# KEYb_final-rev01.net
KiCad netlist of a schematic drawn in EAGLE
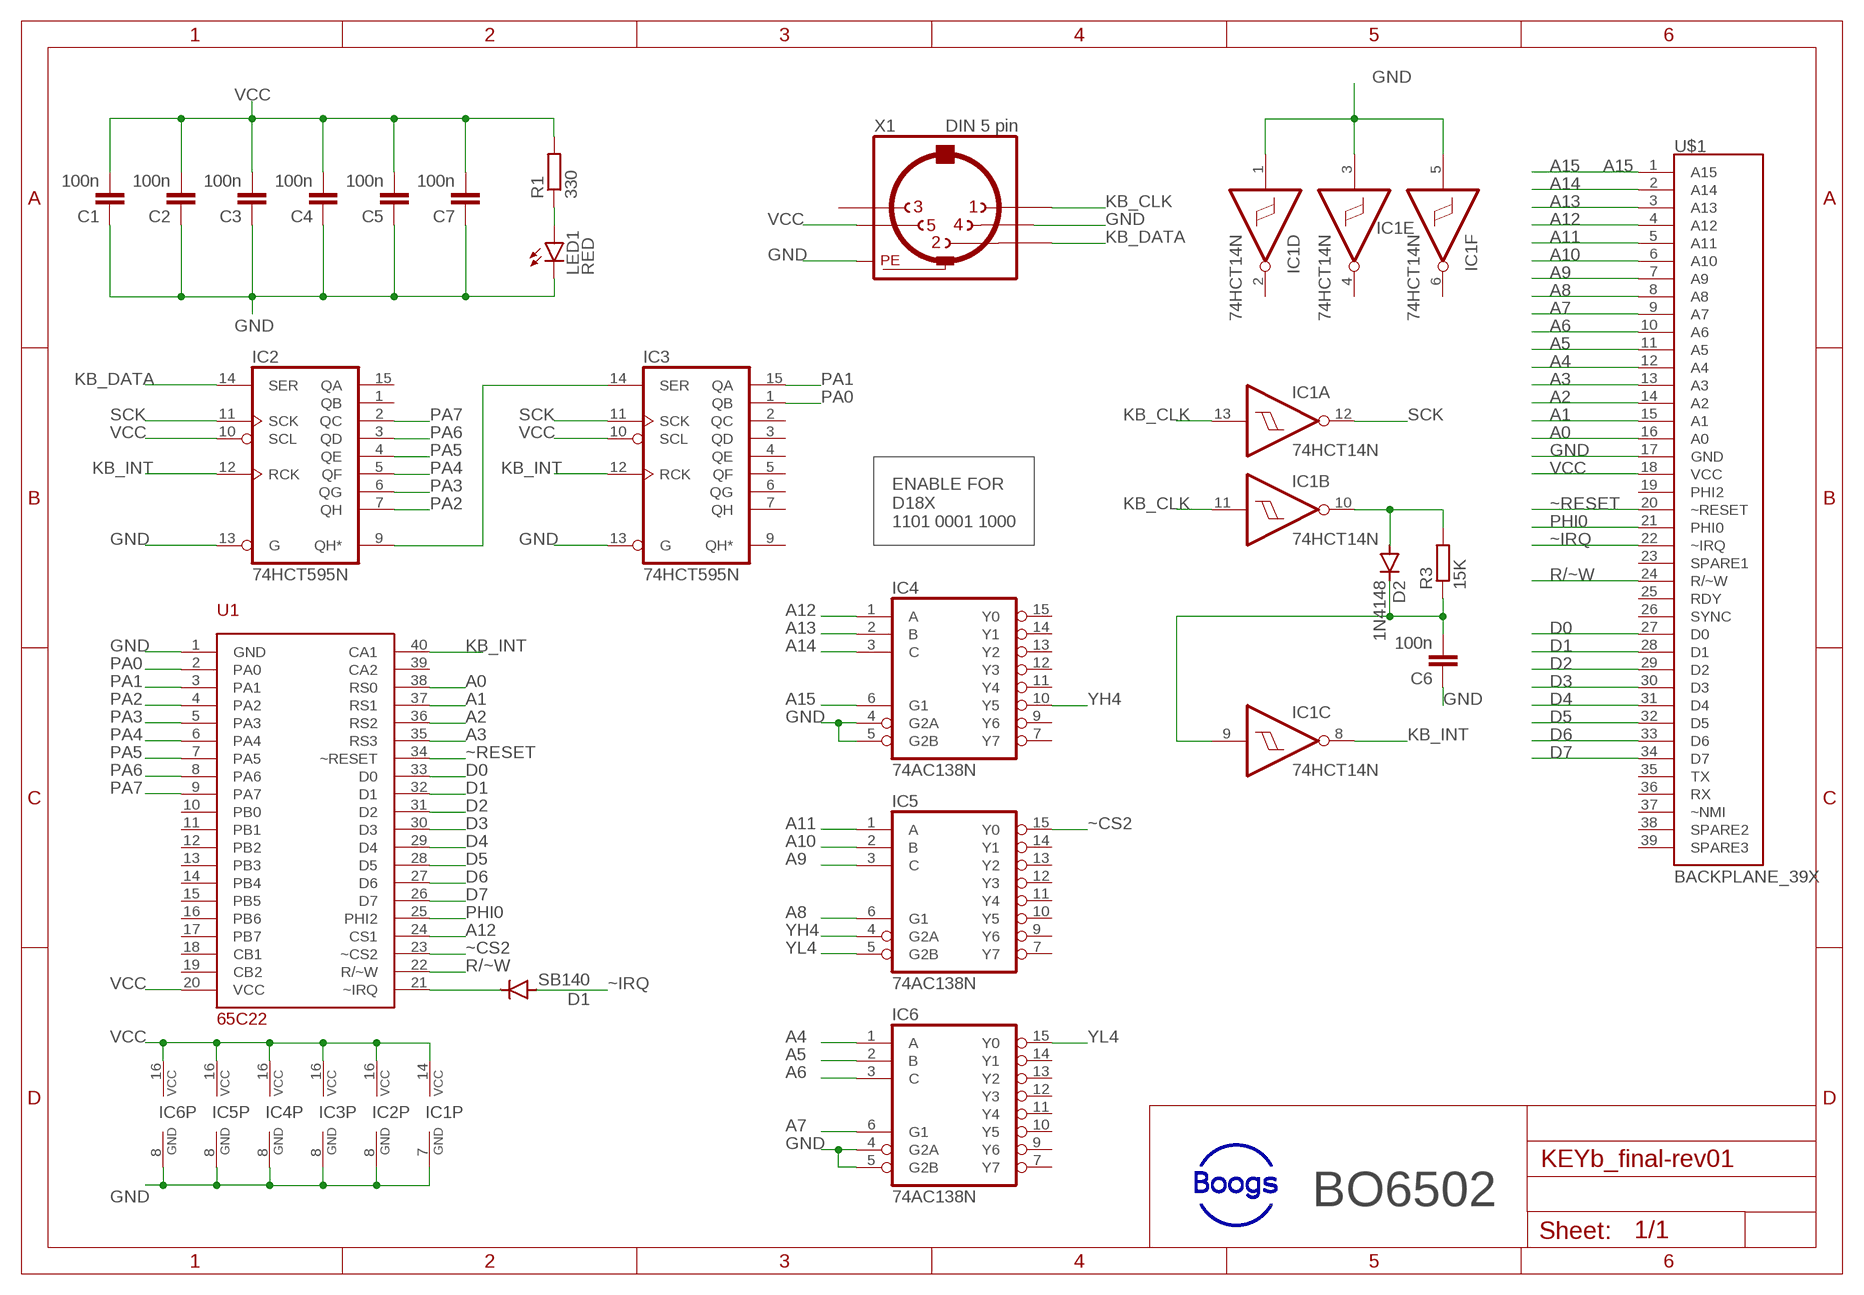
[diagram p0: schematic, sheet 1]

(export (version "E")
  (design (tool "Eeschema 10.0.6"))
  (components
    (comp (ref "C1")
      (value "100n")
      (footprint "eagle-import:C025-025X050")
      (libsource (lib "eagle-import") (part "C-EU025-025X050"))
    )
    (comp (ref "C2")
      (value "100n")
      (footprint "eagle-import:C025-025X050")
      (libsource (lib "eagle-import") (part "C-EU025-025X050"))
    )
    (comp (ref "C3")
      (value "100n")
      (footprint "eagle-import:C025-025X050")
      (libsource (lib "eagle-import") (part "C-EU025-025X050"))
    )
    (comp (ref "C4")
      (value "100n")
      (footprint "eagle-import:C025-025X050")
      (libsource (lib "eagle-import") (part "C-EU025-025X050"))
    )
    (comp (ref "C5")
      (value "100n")
      (footprint "eagle-import:C025-025X050")
      (libsource (lib "eagle-import") (part "C-EU025-025X050"))
    )
    (comp (ref "C6")
      (value "100n")
      (footprint "eagle-import:C025-025X050")
      (libsource (lib "eagle-import") (part "C-EU025-025X050"))
    )
    (comp (ref "C7")
      (value "100n")
      (footprint "eagle-import:C025-025X050")
      (libsource (lib "eagle-import") (part "C-EU025-025X050"))
    )
    (comp (ref "D1")
      (value "SB140")
      (footprint "eagle-import:DO41-10")
      (libsource (lib "eagle-import") (part "1N4004"))
    )
    (comp (ref "D2")
      (value "1N4148")
      (footprint "eagle-import:DO35-7")
      (libsource (lib "eagle-import") (part "1N4148DO35-7"))
    )
    (comp (ref "IC1")
      (value "74HCT14N")
      (footprint "eagle-import:DIL14")
      (libsource (lib "eagle-import") (part "7414NHCT"))
    )
    (comp (ref "IC2")
      (value "74HCT595N")
      (footprint "eagle-import:DIL16")
      (libsource (lib "eagle-import") (part "74595NHCT"))
    )
    (comp (ref "IC3")
      (value "74HCT595N")
      (footprint "eagle-import:DIL16")
      (libsource (lib "eagle-import") (part "74595NHCT"))
    )
    (comp (ref "IC4")
      (value "74AC138N")
      (footprint "eagle-import:DIL16")
      (libsource (lib "eagle-import") (part "74138NAC"))
    )
    (comp (ref "IC5")
      (value "74AC138N")
      (footprint "eagle-import:DIL16")
      (libsource (lib "eagle-import") (part "74138NAC"))
    )
    (comp (ref "IC6")
      (value "74AC138N")
      (footprint "eagle-import:DIL16")
      (libsource (lib "eagle-import") (part "74138NAC"))
    )
    (comp (ref "LED1")
      (value "RED")
      (footprint "eagle-import:LED5MM")
      (libsource (lib "eagle-import") (part "LED5MM"))
    )
    (comp (ref "R1")
      (value "330")
      (footprint "eagle-import:0207_10")
      (libsource (lib "eagle-import") (part "R-EU_0207/10"))
    )
    (comp (ref "R3")
      (value "15K")
      (footprint "eagle-import:0207_10")
      (libsource (lib "eagle-import") (part "R-EU_0207/10"))
    )
    (comp (ref "U$1")
      (value "BACKPLANE_39X")
      (footprint "eagle-import:BP_39X")
      (fields (field (name "A15") "A15"))
      (libsource (lib "eagle-import") (part "BACKPLANE_39X"))
    )
    (comp (ref "U1")
      (value "65C22")
      (footprint "eagle-import:DIL40")
      (libsource (lib "eagle-import") (part "65C22"))
    )
    (comp (ref "X1")
      (value "DIN 5 pin")
      (footprint "eagle-import:MAB5SH")
      (libsource (lib "eagle-import") (part "MAB5SH"))
    )
  )
  (nets
    (net (code "1") (name "/A0") (class "Default")
      (node (ref "U$1") (pin "16") (pinfunction "A0_16") (pintype "bidirectional"))
      (node (ref "U1") (pin "38") (pinfunction "RS0_38") (pintype "bidirectional"))
    )
    (net (code "2") (name "/A1") (class "Default")
      (node (ref "U$1") (pin "15") (pinfunction "A1_15") (pintype "bidirectional"))
      (node (ref "U1") (pin "37") (pinfunction "RS1_37") (pintype "bidirectional"))
    )
    (net (code "3") (name "/A2") (class "Default")
      (node (ref "U$1") (pin "14") (pinfunction "A2_14") (pintype "bidirectional"))
      (node (ref "U1") (pin "36") (pinfunction "RS2_36") (pintype "bidirectional"))
    )
    (net (code "4") (name "/A3") (class "Default")
      (node (ref "U$1") (pin "13") (pinfunction "A3_13") (pintype "bidirectional"))
      (node (ref "U1") (pin "35") (pinfunction "RS3_35") (pintype "bidirectional"))
    )
    (net (code "5") (name "/A4") (class "Default")
      (node (ref "IC6") (pin "1") (pinfunction "A_1") (pintype "input"))
      (node (ref "U$1") (pin "12") (pinfunction "A4_12") (pintype "bidirectional"))
    )
    (net (code "6") (name "/A5") (class "Default")
      (node (ref "IC6") (pin "2") (pinfunction "B_2") (pintype "input"))
      (node (ref "U$1") (pin "11") (pinfunction "A5_11") (pintype "bidirectional"))
    )
    (net (code "7") (name "/A6") (class "Default")
      (node (ref "IC6") (pin "3") (pinfunction "C_3") (pintype "input"))
      (node (ref "U$1") (pin "10") (pinfunction "A6_10") (pintype "bidirectional"))
    )
    (net (code "8") (name "/A7") (class "Default")
      (node (ref "IC6") (pin "6") (pinfunction "G1_6") (pintype "input"))
      (node (ref "U$1") (pin "9") (pinfunction "A7_9") (pintype "bidirectional"))
    )
    (net (code "9") (name "/A8") (class "Default")
      (node (ref "IC5") (pin "6") (pinfunction "G1_6") (pintype "input"))
      (node (ref "U$1") (pin "8") (pinfunction "A8_8") (pintype "bidirectional"))
    )
    (net (code "10") (name "/A9") (class "Default")
      (node (ref "IC5") (pin "3") (pinfunction "C_3") (pintype "input"))
      (node (ref "U$1") (pin "7") (pinfunction "A9_7") (pintype "bidirectional"))
    )
    (net (code "11") (name "/A10") (class "Default")
      (node (ref "IC5") (pin "2") (pinfunction "B_2") (pintype "input"))
      (node (ref "U$1") (pin "6") (pinfunction "A10_6") (pintype "bidirectional"))
    )
    (net (code "12") (name "/A11") (class "Default")
      (node (ref "IC5") (pin "1") (pinfunction "A_1") (pintype "input"))
      (node (ref "U$1") (pin "5") (pinfunction "A11_5") (pintype "bidirectional"))
    )
    (net (code "13") (name "/A12") (class "Default")
      (node (ref "IC4") (pin "1") (pinfunction "A_1") (pintype "input"))
      (node (ref "U$1") (pin "4") (pinfunction "A12_4") (pintype "bidirectional"))
      (node (ref "U1") (pin "24") (pinfunction "CS1_24") (pintype "bidirectional"))
    )
    (net (code "14") (name "/A13") (class "Default")
      (node (ref "IC4") (pin "2") (pinfunction "B_2") (pintype "input"))
      (node (ref "U$1") (pin "3") (pinfunction "A13_3") (pintype "bidirectional"))
    )
    (net (code "15") (name "/A14") (class "Default")
      (node (ref "IC4") (pin "3") (pinfunction "C_3") (pintype "input"))
      (node (ref "U$1") (pin "2") (pinfunction "A14_2") (pintype "bidirectional"))
    )
    (net (code "16") (name "/A15") (class "Default")
      (node (ref "IC4") (pin "6") (pinfunction "G1_6") (pintype "input"))
      (node (ref "U$1") (pin "1") (pinfunction "A15_1") (pintype "bidirectional"))
    )
    (net (code "17") (name "/D0") (class "Default")
      (node (ref "U$1") (pin "27") (pinfunction "D0_27") (pintype "bidirectional"))
      (node (ref "U1") (pin "33") (pinfunction "D0_33") (pintype "bidirectional"))
    )
    (net (code "18") (name "/D1") (class "Default")
      (node (ref "U$1") (pin "28") (pinfunction "D1_28") (pintype "bidirectional"))
      (node (ref "U1") (pin "32") (pinfunction "D1_32") (pintype "bidirectional"))
    )
    (net (code "19") (name "/D2") (class "Default")
      (node (ref "U$1") (pin "29") (pinfunction "D2_29") (pintype "bidirectional"))
      (node (ref "U1") (pin "31") (pinfunction "D2_31") (pintype "bidirectional"))
    )
    (net (code "20") (name "/D3") (class "Default")
      (node (ref "U$1") (pin "30") (pinfunction "D3_30") (pintype "bidirectional"))
      (node (ref "U1") (pin "30") (pinfunction "D3_30") (pintype "bidirectional"))
    )
    (net (code "21") (name "/D4") (class "Default")
      (node (ref "U$1") (pin "31") (pinfunction "D4_31") (pintype "bidirectional"))
      (node (ref "U1") (pin "29") (pinfunction "D4_29") (pintype "bidirectional"))
    )
    (net (code "22") (name "/D5") (class "Default")
      (node (ref "U$1") (pin "32") (pinfunction "D5_32") (pintype "bidirectional"))
      (node (ref "U1") (pin "28") (pinfunction "D5_28") (pintype "bidirectional"))
    )
    (net (code "23") (name "/D6") (class "Default")
      (node (ref "U$1") (pin "33") (pinfunction "D6_33") (pintype "bidirectional"))
      (node (ref "U1") (pin "27") (pinfunction "D6_27") (pintype "bidirectional"))
    )
    (net (code "24") (name "/D7") (class "Default")
      (node (ref "U$1") (pin "34") (pinfunction "D7_34") (pintype "bidirectional"))
      (node (ref "U1") (pin "26") (pinfunction "D7_26") (pintype "bidirectional"))
    )
    (net (code "25") (name "/GND") (class "Default")
      (node (ref "C1") (pin "1") (pinfunction "1_1") (pintype "passive"))
      (node (ref "C2") (pin "1") (pinfunction "1_1") (pintype "passive"))
      (node (ref "C3") (pin "1") (pinfunction "1_1") (pintype "passive"))
      (node (ref "C4") (pin "1") (pinfunction "1_1") (pintype "passive"))
      (node (ref "C5") (pin "1") (pinfunction "1_1") (pintype "passive"))
      (node (ref "C6") (pin "1") (pinfunction "1_1") (pintype "passive"))
      (node (ref "C7") (pin "1") (pinfunction "1_1") (pintype "passive"))
      (node (ref "IC1") (pin "1") (pinfunction "I_1") (pintype "input"))
      (node (ref "IC1") (pin "3") (pinfunction "I_3") (pintype "input"))
      (node (ref "IC1") (pin "5") (pinfunction "I_5") (pintype "input"))
      (node (ref "IC1") (pin "7") (pinfunction "GND_7") (pintype "power_in"))
      (node (ref "IC2") (pin "13") (pinfunction "G_13") (pintype "input"))
      (node (ref "IC2") (pin "8") (pinfunction "GND_8") (pintype "power_in"))
      (node (ref "IC3") (pin "13") (pinfunction "G_13") (pintype "input"))
      (node (ref "IC3") (pin "8") (pinfunction "GND_8") (pintype "power_in"))
      (node (ref "IC4") (pin "4") (pinfunction "G2A_4") (pintype "input"))
      (node (ref "IC4") (pin "5") (pinfunction "G2B_5") (pintype "input"))
      (node (ref "IC4") (pin "8") (pinfunction "GND_8") (pintype "power_in"))
      (node (ref "IC5") (pin "8") (pinfunction "GND_8") (pintype "power_in"))
      (node (ref "IC6") (pin "4") (pinfunction "G2A_4") (pintype "input"))
      (node (ref "IC6") (pin "5") (pinfunction "G2B_5") (pintype "input"))
      (node (ref "IC6") (pin "8") (pinfunction "GND_8") (pintype "power_in"))
      (node (ref "LED1") (pin "K") (pinfunction "C_K") (pintype "passive"))
      (node (ref "U$1") (pin "17") (pinfunction "GND_17") (pintype "bidirectional"))
      (node (ref "U1") (pin "1") (pinfunction "GND_1") (pintype "bidirectional"))
      (node (ref "X1") (pin "4") (pinfunction "4_4") (pintype "passive"))
      (node (ref "X1") (pin "PE") (pinfunction "PE_PE") (pintype "power_in"))
      (node (ref "X1") (pin "PE@") (pinfunction "PE_PE@") (pintype "power_in"))
    )
    (net (code "26") (name "/KB_CLK") (class "Default")
      (node (ref "IC1") (pin "11") (pinfunction "I_11") (pintype "input"))
      (node (ref "IC1") (pin "13") (pinfunction "I_13") (pintype "input"))
      (node (ref "X1") (pin "1") (pinfunction "1_1") (pintype "passive"))
    )
    (net (code "27") (name "/KB_DATA") (class "Default")
      (node (ref "IC2") (pin "14") (pinfunction "SER_14") (pintype "input"))
      (node (ref "X1") (pin "2") (pinfunction "2_2") (pintype "passive"))
    )
    (net (code "28") (name "/KB_INT") (class "Default")
      (node (ref "IC1") (pin "8") (pinfunction "O_8") (pintype "output"))
      (node (ref "IC2") (pin "12") (pinfunction "RCK_12") (pintype "input"))
      (node (ref "IC3") (pin "12") (pinfunction "RCK_12") (pintype "input"))
      (node (ref "U1") (pin "40") (pinfunction "CA1_40") (pintype "bidirectional"))
    )
    (net (code "29") (name "/PA0") (class "Default")
      (node (ref "IC3") (pin "1") (pinfunction "QB_1") (pintype "tri_state"))
      (node (ref "U1") (pin "2") (pinfunction "PA0_2") (pintype "bidirectional"))
    )
    (net (code "30") (name "/PA1") (class "Default")
      (node (ref "IC3") (pin "15") (pinfunction "QA_15") (pintype "tri_state"))
      (node (ref "U1") (pin "3") (pinfunction "PA1_3") (pintype "bidirectional"))
    )
    (net (code "31") (name "/PA2") (class "Default")
      (node (ref "IC2") (pin "7") (pinfunction "QH_7") (pintype "tri_state"))
      (node (ref "U1") (pin "4") (pinfunction "PA2_4") (pintype "bidirectional"))
    )
    (net (code "32") (name "/PA3") (class "Default")
      (node (ref "IC2") (pin "6") (pinfunction "QG_6") (pintype "tri_state"))
      (node (ref "U1") (pin "5") (pinfunction "PA3_5") (pintype "bidirectional"))
    )
    (net (code "33") (name "/PA4") (class "Default")
      (node (ref "IC2") (pin "5") (pinfunction "QF_5") (pintype "tri_state"))
      (node (ref "U1") (pin "6") (pinfunction "PA4_6") (pintype "bidirectional"))
    )
    (net (code "34") (name "/PA5") (class "Default")
      (node (ref "IC2") (pin "4") (pinfunction "QE_4") (pintype "tri_state"))
      (node (ref "U1") (pin "7") (pinfunction "PA5_7") (pintype "bidirectional"))
    )
    (net (code "35") (name "/PA6") (class "Default")
      (node (ref "IC2") (pin "3") (pinfunction "QD_3") (pintype "tri_state"))
      (node (ref "U1") (pin "8") (pinfunction "PA6_8") (pintype "bidirectional"))
    )
    (net (code "36") (name "/PA7") (class "Default")
      (node (ref "IC2") (pin "2") (pinfunction "QC_2") (pintype "tri_state"))
      (node (ref "U1") (pin "9") (pinfunction "PA7_9") (pintype "bidirectional"))
    )
    (net (code "37") (name "/PHI0") (class "Default")
      (node (ref "U$1") (pin "21") (pinfunction "PHI0_21") (pintype "bidirectional"))
      (node (ref "U1") (pin "25") (pinfunction "PHI2_25") (pintype "bidirectional"))
    )
    (net (code "38") (name "/R{slash}~{W}") (class "Default")
      (node (ref "U$1") (pin "24") (pinfunction "R/~{W}_24") (pintype "bidirectional"))
      (node (ref "U1") (pin "22") (pinfunction "R/~{W}_22") (pintype "bidirectional"))
    )
    (net (code "39") (name "/SCK") (class "Default")
      (node (ref "IC1") (pin "12") (pinfunction "O_12") (pintype "output"))
      (node (ref "IC2") (pin "11") (pinfunction "SCK_11") (pintype "input"))
      (node (ref "IC3") (pin "11") (pinfunction "SCK_11") (pintype "input"))
    )
    (net (code "40") (name "/VCC") (class "Default")
      (node (ref "C1") (pin "2") (pinfunction "2_2") (pintype "passive"))
      (node (ref "C2") (pin "2") (pinfunction "2_2") (pintype "passive"))
      (node (ref "C3") (pin "2") (pinfunction "2_2") (pintype "passive"))
      (node (ref "C4") (pin "2") (pinfunction "2_2") (pintype "passive"))
      (node (ref "C5") (pin "2") (pinfunction "2_2") (pintype "passive"))
      (node (ref "C7") (pin "2") (pinfunction "2_2") (pintype "passive"))
      (node (ref "IC1") (pin "14") (pinfunction "VCC_14") (pintype "power_in"))
      (node (ref "IC2") (pin "10") (pinfunction "SCL_10") (pintype "input"))
      (node (ref "IC2") (pin "16") (pinfunction "VCC_16") (pintype "power_in"))
      (node (ref "IC3") (pin "10") (pinfunction "SCL_10") (pintype "input"))
      (node (ref "IC3") (pin "16") (pinfunction "VCC_16") (pintype "power_in"))
      (node (ref "IC4") (pin "16") (pinfunction "VCC_16") (pintype "power_in"))
      (node (ref "IC5") (pin "16") (pinfunction "VCC_16") (pintype "power_in"))
      (node (ref "IC6") (pin "16") (pinfunction "VCC_16") (pintype "power_in"))
      (node (ref "R1") (pin "2") (pinfunction "2_2") (pintype "passive"))
      (node (ref "U$1") (pin "18") (pinfunction "VCC_18") (pintype "bidirectional"))
      (node (ref "U1") (pin "20") (pinfunction "VCC_20") (pintype "bidirectional"))
      (node (ref "X1") (pin "5") (pinfunction "5_5") (pintype "passive"))
    )
    (net (code "41") (name "/YH4") (class "Default")
      (node (ref "IC4") (pin "10") (pinfunction "Y5_10") (pintype "output"))
      (node (ref "IC5") (pin "4") (pinfunction "G2A_4") (pintype "input"))
    )
    (net (code "42") (name "/YL4") (class "Default")
      (node (ref "IC5") (pin "5") (pinfunction "G2B_5") (pintype "input"))
      (node (ref "IC6") (pin "15") (pinfunction "Y0_15") (pintype "output"))
    )
    (net (code "43") (name "/~{CS2}") (class "Default")
      (node (ref "IC5") (pin "15") (pinfunction "Y0_15") (pintype "output"))
      (node (ref "U1") (pin "23") (pinfunction "~{CS2}_23") (pintype "bidirectional"))
    )
    (net (code "44") (name "/~{IRQ}") (class "Default")
      (node (ref "D1") (pin "A") (pinfunction "A_A") (pintype "passive"))
      (node (ref "U$1") (pin "22") (pinfunction "~{IRQ}_22") (pintype "bidirectional"))
    )
    (net (code "45") (name "/~{RESET}") (class "Default")
      (node (ref "U$1") (pin "20") (pinfunction "~{RESET}_20") (pintype "bidirectional"))
      (node (ref "U1") (pin "34") (pinfunction "~{RESET}_34") (pintype "bidirectional"))
    )
    (net (code "46") (name "Net-(IC1B-O)") (class "Default")
      (node (ref "D2") (pin "A") (pinfunction "A_A") (pintype "passive"))
      (node (ref "IC1") (pin "10") (pinfunction "O_10") (pintype "output"))
      (node (ref "R3") (pin "2") (pinfunction "2_2") (pintype "passive"))
    )
    (net (code "47") (name "Net-(IC1C-I)") (class "Default")
      (node (ref "C6") (pin "2") (pinfunction "2_2") (pintype "passive"))
      (node (ref "D2") (pin "C") (pinfunction "C_C") (pintype "passive"))
      (node (ref "IC1") (pin "9") (pinfunction "I_9") (pintype "input"))
      (node (ref "R3") (pin "1") (pinfunction "1_1") (pintype "passive"))
    )
    (net (code "48") (name "Net-(IC2A-QH*)") (class "Default")
      (node (ref "IC2") (pin "9") (pinfunction "QH*_9") (pintype "tri_state"))
      (node (ref "IC3") (pin "14") (pinfunction "SER_14") (pintype "input"))
    )
    (net (code "49") (name "Net-(LED1-PadA)") (class "Default")
      (node (ref "LED1") (pin "A") (pinfunction "A_A") (pintype "passive"))
      (node (ref "R1") (pin "1") (pinfunction "1_1") (pintype "passive"))
    )
    (net (code "50") (name "Net-(U1-~{IRQ})") (class "Default")
      (node (ref "D1") (pin "C") (pinfunction "C_C") (pintype "passive"))
      (node (ref "U1") (pin "21") (pinfunction "~{IRQ}_21") (pintype "bidirectional"))
    )
    (net (code "51") (name "unconnected-(IC1D-O-Pad2)") (class "Default")
      (node (ref "IC1") (pin "2") (pinfunction "O_2") (pintype "output"))
    )
    (net (code "52") (name "unconnected-(IC1E-O-Pad4)") (class "Default")
      (node (ref "IC1") (pin "4") (pinfunction "O_4") (pintype "output"))
    )
    (net (code "53") (name "unconnected-(IC1F-O-Pad6)") (class "Default")
      (node (ref "IC1") (pin "6") (pinfunction "O_6") (pintype "output"))
    )
    (net (code "54") (name "unconnected-(IC2A-QA-Pad15)") (class "Default")
      (node (ref "IC2") (pin "15") (pinfunction "QA_15") (pintype "tri_state"))
    )
    (net (code "55") (name "unconnected-(IC2A-QB-Pad1)") (class "Default")
      (node (ref "IC2") (pin "1") (pinfunction "QB_1") (pintype "tri_state"))
    )
    (net (code "56") (name "unconnected-(IC3A-QC-Pad2)") (class "Default")
      (node (ref "IC3") (pin "2") (pinfunction "QC_2") (pintype "tri_state"))
    )
    (net (code "57") (name "unconnected-(IC3A-QD-Pad3)") (class "Default")
      (node (ref "IC3") (pin "3") (pinfunction "QD_3") (pintype "tri_state"))
    )
    (net (code "58") (name "unconnected-(IC3A-QE-Pad4)") (class "Default")
      (node (ref "IC3") (pin "4") (pinfunction "QE_4") (pintype "tri_state"))
    )
    (net (code "59") (name "unconnected-(IC3A-QF-Pad5)") (class "Default")
      (node (ref "IC3") (pin "5") (pinfunction "QF_5") (pintype "tri_state"))
    )
    (net (code "60") (name "unconnected-(IC3A-QG-Pad6)") (class "Default")
      (node (ref "IC3") (pin "6") (pinfunction "QG_6") (pintype "tri_state"))
    )
    (net (code "61") (name "unconnected-(IC3A-QH*-Pad9)") (class "Default")
      (node (ref "IC3") (pin "9") (pinfunction "QH*_9") (pintype "tri_state"))
    )
    (net (code "62") (name "unconnected-(IC3A-QH-Pad7)") (class "Default")
      (node (ref "IC3") (pin "7") (pinfunction "QH_7") (pintype "tri_state"))
    )
    (net (code "63") (name "unconnected-(IC4A-Y0-Pad15)") (class "Default")
      (node (ref "IC4") (pin "15") (pinfunction "Y0_15") (pintype "output"))
    )
    (net (code "64") (name "unconnected-(IC4A-Y1-Pad14)") (class "Default")
      (node (ref "IC4") (pin "14") (pinfunction "Y1_14") (pintype "output"))
    )
    (net (code "65") (name "unconnected-(IC4A-Y2-Pad13)") (class "Default")
      (node (ref "IC4") (pin "13") (pinfunction "Y2_13") (pintype "output"))
    )
    (net (code "66") (name "unconnected-(IC4A-Y3-Pad12)") (class "Default")
      (node (ref "IC4") (pin "12") (pinfunction "Y3_12") (pintype "output"))
    )
    (net (code "67") (name "unconnected-(IC4A-Y4-Pad11)") (class "Default")
      (node (ref "IC4") (pin "11") (pinfunction "Y4_11") (pintype "output"))
    )
    (net (code "68") (name "unconnected-(IC4A-Y6-Pad9)") (class "Default")
      (node (ref "IC4") (pin "9") (pinfunction "Y6_9") (pintype "output"))
    )
    (net (code "69") (name "unconnected-(IC4A-Y7-Pad7)") (class "Default")
      (node (ref "IC4") (pin "7") (pinfunction "Y7_7") (pintype "output"))
    )
    (net (code "70") (name "unconnected-(IC5A-Y1-Pad14)") (class "Default")
      (node (ref "IC5") (pin "14") (pinfunction "Y1_14") (pintype "output"))
    )
    (net (code "71") (name "unconnected-(IC5A-Y2-Pad13)") (class "Default")
      (node (ref "IC5") (pin "13") (pinfunction "Y2_13") (pintype "output"))
    )
    (net (code "72") (name "unconnected-(IC5A-Y3-Pad12)") (class "Default")
      (node (ref "IC5") (pin "12") (pinfunction "Y3_12") (pintype "output"))
    )
    (net (code "73") (name "unconnected-(IC5A-Y4-Pad11)") (class "Default")
      (node (ref "IC5") (pin "11") (pinfunction "Y4_11") (pintype "output"))
    )
    (net (code "74") (name "unconnected-(IC5A-Y5-Pad10)") (class "Default")
      (node (ref "IC5") (pin "10") (pinfunction "Y5_10") (pintype "output"))
    )
    (net (code "75") (name "unconnected-(IC5A-Y6-Pad9)") (class "Default")
      (node (ref "IC5") (pin "9") (pinfunction "Y6_9") (pintype "output"))
    )
    (net (code "76") (name "unconnected-(IC5A-Y7-Pad7)") (class "Default")
      (node (ref "IC5") (pin "7") (pinfunction "Y7_7") (pintype "output"))
    )
    (net (code "77") (name "unconnected-(IC6A-Y1-Pad14)") (class "Default")
      (node (ref "IC6") (pin "14") (pinfunction "Y1_14") (pintype "output"))
    )
    (net (code "78") (name "unconnected-(IC6A-Y2-Pad13)") (class "Default")
      (node (ref "IC6") (pin "13") (pinfunction "Y2_13") (pintype "output"))
    )
    (net (code "79") (name "unconnected-(IC6A-Y3-Pad12)") (class "Default")
      (node (ref "IC6") (pin "12") (pinfunction "Y3_12") (pintype "output"))
    )
    (net (code "80") (name "unconnected-(IC6A-Y4-Pad11)") (class "Default")
      (node (ref "IC6") (pin "11") (pinfunction "Y4_11") (pintype "output"))
    )
    (net (code "81") (name "unconnected-(IC6A-Y5-Pad10)") (class "Default")
      (node (ref "IC6") (pin "10") (pinfunction "Y5_10") (pintype "output"))
    )
    (net (code "82") (name "unconnected-(IC6A-Y6-Pad9)") (class "Default")
      (node (ref "IC6") (pin "9") (pinfunction "Y6_9") (pintype "output"))
    )
    (net (code "83") (name "unconnected-(IC6A-Y7-Pad7)") (class "Default")
      (node (ref "IC6") (pin "7") (pinfunction "Y7_7") (pintype "output"))
    )
    (net (code "84") (name "unconnected-(U$1-PHI2-Pad19)") (class "Default")
      (node (ref "U$1") (pin "19") (pinfunction "PHI2_19") (pintype "bidirectional"))
    )
    (net (code "85") (name "unconnected-(U$1-RDY-Pad25)") (class "Default")
      (node (ref "U$1") (pin "25") (pinfunction "RDY_25") (pintype "bidirectional"))
    )
    (net (code "86") (name "unconnected-(U$1-RX-Pad36)") (class "Default")
      (node (ref "U$1") (pin "36") (pinfunction "RX_36") (pintype "bidirectional"))
    )
    (net (code "87") (name "unconnected-(U$1-SPARE1-Pad23)") (class "Default")
      (node (ref "U$1") (pin "23") (pinfunction "SPARE1_23") (pintype "bidirectional"))
    )
    (net (code "88") (name "unconnected-(U$1-SPARE2-Pad38)") (class "Default")
      (node (ref "U$1") (pin "38") (pinfunction "SPARE2_38") (pintype "bidirectional"))
    )
    (net (code "89") (name "unconnected-(U$1-SPARE3-Pad39)") (class "Default")
      (node (ref "U$1") (pin "39") (pinfunction "SPARE3_39") (pintype "bidirectional"))
    )
    (net (code "90") (name "unconnected-(U$1-SYNC-Pad26)") (class "Default")
      (node (ref "U$1") (pin "26") (pinfunction "SYNC_26") (pintype "bidirectional"))
    )
    (net (code "91") (name "unconnected-(U$1-TX-Pad35)") (class "Default")
      (node (ref "U$1") (pin "35") (pinfunction "TX_35") (pintype "bidirectional"))
    )
    (net (code "92") (name "unconnected-(U$1-~{NMI}-Pad37)") (class "Default")
      (node (ref "U$1") (pin "37") (pinfunction "~{NMI}_37") (pintype "bidirectional"))
    )
    (net (code "93") (name "unconnected-(U1-CA2-Pad39)") (class "Default")
      (node (ref "U1") (pin "39") (pinfunction "CA2_39") (pintype "bidirectional"))
    )
    (net (code "94") (name "unconnected-(U1-CB1-Pad18)") (class "Default")
      (node (ref "U1") (pin "18") (pinfunction "CB1_18") (pintype "bidirectional"))
    )
    (net (code "95") (name "unconnected-(U1-CB2-Pad19)") (class "Default")
      (node (ref "U1") (pin "19") (pinfunction "CB2_19") (pintype "bidirectional"))
    )
    (net (code "96") (name "unconnected-(U1-PB0-Pad10)") (class "Default")
      (node (ref "U1") (pin "10") (pinfunction "PB0_10") (pintype "bidirectional"))
    )
    (net (code "97") (name "unconnected-(U1-PB1-Pad11)") (class "Default")
      (node (ref "U1") (pin "11") (pinfunction "PB1_11") (pintype "bidirectional"))
    )
    (net (code "98") (name "unconnected-(U1-PB2-Pad12)") (class "Default")
      (node (ref "U1") (pin "12") (pinfunction "PB2_12") (pintype "bidirectional"))
    )
    (net (code "99") (name "unconnected-(U1-PB3-Pad13)") (class "Default")
      (node (ref "U1") (pin "13") (pinfunction "PB3_13") (pintype "bidirectional"))
    )
    (net (code "100") (name "unconnected-(U1-PB4-Pad14)") (class "Default")
      (node (ref "U1") (pin "14") (pinfunction "PB4_14") (pintype "bidirectional"))
    )
    (net (code "101") (name "unconnected-(U1-PB5-Pad15)") (class "Default")
      (node (ref "U1") (pin "15") (pinfunction "PB5_15") (pintype "bidirectional"))
    )
    (net (code "102") (name "unconnected-(U1-PB6-Pad16)") (class "Default")
      (node (ref "U1") (pin "16") (pinfunction "PB6_16") (pintype "bidirectional"))
    )
    (net (code "103") (name "unconnected-(U1-PB7-Pad17)") (class "Default")
      (node (ref "U1") (pin "17") (pinfunction "PB7_17") (pintype "bidirectional"))
    )
    (net (code "104") (name "unconnected-(X1-Pad3)") (class "Default")
      (node (ref "X1") (pin "3") (pinfunction "3_3") (pintype "passive"))
    )
  )
)
